# controle_com_2dimmer.net
KiCad netlist of a schematic drawn in EAGLE
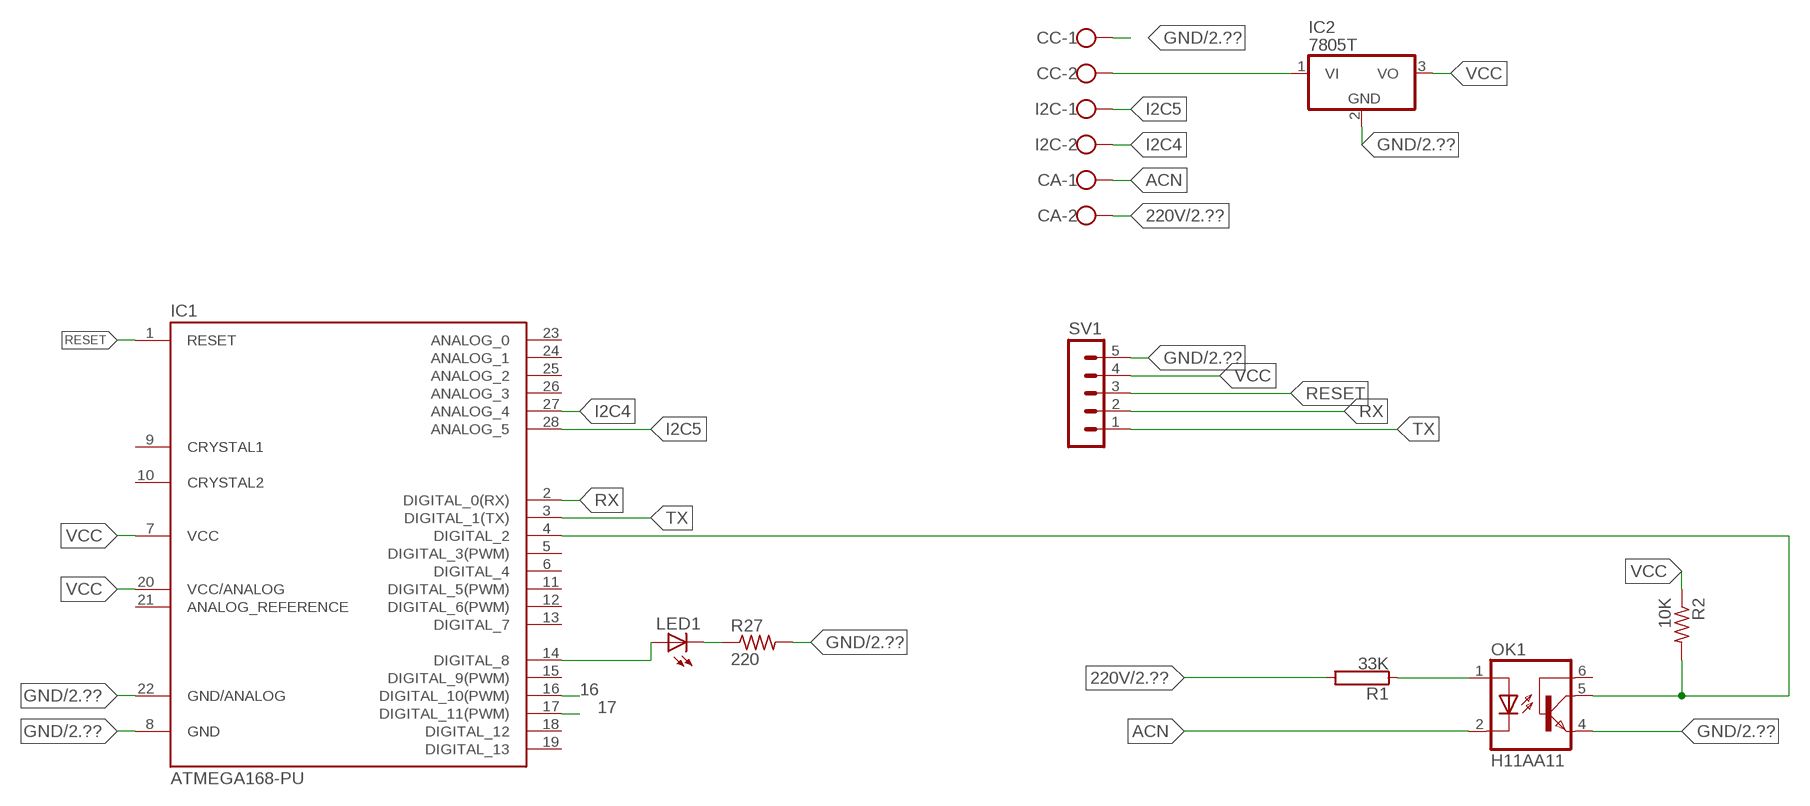
[diagram p0: schematic, sheet 1]
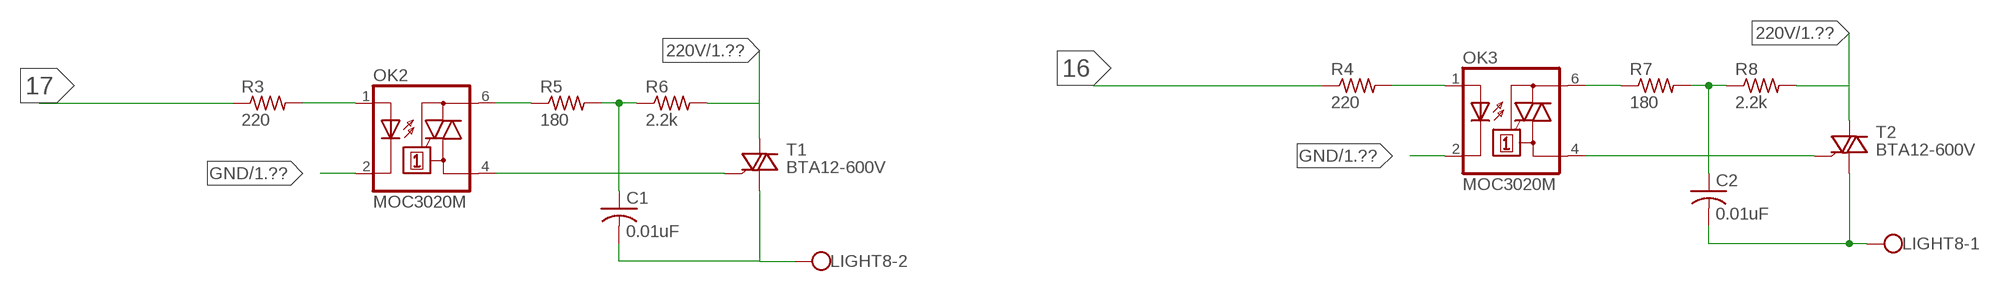
[diagram p1: schematic, sheet 2]

(export (version "E")
  (design (tool "Eeschema 10.0.6"))
  (components
    (comp (ref "CA")
      (value "W237-102")
      (footprint "eagle-import:W237-102")
      (fields (field (name "MPN") "237-102"))
      (libsource (lib "eagle-import") (part "W237-102"))
    )
    (comp (ref "CC")
      (value "W237-102")
      (footprint "eagle-import:W237-102")
      (fields (field (name "MPN") "237-102"))
      (libsource (lib "eagle-import") (part "W237-102"))
    )
    (comp (ref "I2C")
      (value "W237-102")
      (footprint "eagle-import:W237-102")
      (fields (field (name "MPN") "237-102"))
      (libsource (lib "eagle-import") (part "W237-102"))
    )
    (comp (ref "IC1")
      (value "ATMEGA168-PU")
      (footprint "eagle-import:DIL28-3")
      (libsource (lib "eagle-import") (part "ATMEGA168-PU"))
    )
    (comp (ref "IC2")
      (value "7805T")
      (footprint "eagle-import:TO220H")
      (libsource (lib "eagle-import") (part "78T05"))
    )
    (comp (ref "LED1")
      (value "LED3MM")
      (footprint "eagle-import:LED3MM")
      (libsource (lib "eagle-import") (part "LED3MM"))
    )
    (comp (ref "OK1")
      (value "H11AA11")
      (footprint "eagle-import:DIL06")
      (fields (field (name "MPN") "H11A1-M"))
      (libsource (lib "eagle-import") (part "H11AA11"))
    )
    (comp (ref "R1")
      (value "33K")
      (footprint "eagle-import:KH206-8R")
      (libsource (lib "eagle-import") (part "RKH206-8R"))
    )
    (comp (ref "R2")
      (value "10K")
      (footprint "eagle-import:0207_7")
      (libsource (lib "eagle-import") (part "R-US_0207/7"))
    )
    (comp (ref "R27")
      (value "220")
      (footprint "eagle-import:0207_7")
      (libsource (lib "eagle-import") (part "R-US_0207/7"))
    )
    (comp (ref "SV1")
      (value "MA05-1")
      (footprint "eagle-import:MA05-1")
      (libsource (lib "eagle-import") (part "MA05-1"))
    )
    (comp (ref "C1")
      (value "0.01uF")
      (footprint "eagle-import:C075-042X103")
      (libsource (lib "eagle-import") (part "C-US075-042X103"))
    )
    (comp (ref "C2")
      (value "0.01uF")
      (footprint "eagle-import:C075-042X103")
      (libsource (lib "eagle-import") (part "C-US075-042X103"))
    )
    (comp (ref "LIGHT8")
      (value "W237-102")
      (footprint "eagle-import:W237-102")
      (fields (field (name "MPN") "237-102"))
      (libsource (lib "eagle-import") (part "W237-102"))
    )
    (comp (ref "OK2")
      (value "MOC3020M")
      (footprint "eagle-import:DIL06")
      (fields (field (name "MF") "FAIRCHILD SEMICONDUCTOR") (field (name "MPN") "MOC3020-M"))
      (libsource (lib "eagle-import") (part "MOC30M20"))
    )
    (comp (ref "OK3")
      (value "MOC3020M")
      (footprint "eagle-import:DIL06")
      (fields (field (name "MF") "FAIRCHILD SEMICONDUCTOR") (field (name "MPN") "MOC3020-M"))
      (libsource (lib "eagle-import") (part "MOC30M20"))
    )
    (comp (ref "R3")
      (value "220")
      (footprint "eagle-import:0207_7")
      (libsource (lib "eagle-import") (part "R-US_0207/7"))
    )
    (comp (ref "R4")
      (value "220")
      (footprint "eagle-import:0207_7")
      (libsource (lib "eagle-import") (part "R-US_0207/7"))
    )
    (comp (ref "R5")
      (value "180")
      (footprint "eagle-import:0309_10")
      (libsource (lib "eagle-import") (part "R-US_0309/10"))
    )
    (comp (ref "R6")
      (value "2.2k")
      (footprint "eagle-import:0309_10")
      (libsource (lib "eagle-import") (part "R-US_0309/10"))
    )
    (comp (ref "R7")
      (value "180")
      (footprint "eagle-import:0309_10")
      (libsource (lib "eagle-import") (part "R-US_0309/10"))
    )
    (comp (ref "R8")
      (value "2.2k")
      (footprint "eagle-import:0309_10")
      (libsource (lib "eagle-import") (part "R-US_0309/10"))
    )
    (comp (ref "T1")
      (value "BTA12-600V")
      (footprint "eagle-import:TO220V")
      (libsource (lib "eagle-import") (part "BTA12-600V"))
    )
    (comp (ref "T2")
      (value "BTA12-600V")
      (footprint "eagle-import:TO220V")
      (libsource (lib "eagle-import") (part "BTA12-600V"))
    )
  )
  (nets
    (net (code "1") (name "16") (class "Default")
      (node (ref "IC1") (pin "16") (pinfunction "DIGITAL_10(PWM)_16") (pintype "bidirectional"))
      (node (ref "R4") (pin "1") (pinfunction "1_1") (pintype "passive"))
    )
    (net (code "2") (name "17") (class "Default")
      (node (ref "IC1") (pin "17") (pinfunction "DIGITAL_11(PWM)_17") (pintype "bidirectional"))
      (node (ref "R3") (pin "1") (pinfunction "1_1") (pintype "passive"))
    )
    (net (code "3") (name "220V") (class "Default")
      (node (ref "CA") (pin "2") (pinfunction "KL_2") (pintype "passive"))
      (node (ref "R1") (pin "2") (pinfunction "2_2") (pintype "passive"))
      (node (ref "R6") (pin "2") (pinfunction "2_2") (pintype "passive"))
      (node (ref "R8") (pin "2") (pinfunction "2_2") (pintype "passive"))
      (node (ref "T1") (pin "2") (pinfunction "A2_2") (pintype "passive"))
      (node (ref "T2") (pin "2") (pinfunction "A2_2") (pintype "passive"))
    )
    (net (code "4") (name "ACN") (class "Default")
      (node (ref "CA") (pin "1") (pinfunction "KL_1") (pintype "passive"))
      (node (ref "OK1") (pin "2") (pinfunction "C_2") (pintype "passive"))
    )
    (net (code "5") (name "GND") (class "Default")
      (node (ref "CC") (pin "1") (pinfunction "KL_1") (pintype "passive"))
      (node (ref "IC1") (pin "22") (pinfunction "GND/ANALOG_22") (pintype "power_in"))
      (node (ref "IC1") (pin "8") (pinfunction "GND_8") (pintype "power_in"))
      (node (ref "IC2") (pin "2") (pinfunction "GND_2") (pintype "passive"))
      (node (ref "OK1") (pin "4") (pinfunction "EMI_4") (pintype "passive"))
      (node (ref "OK2") (pin "2") (pinfunction "C_2") (pintype "passive"))
      (node (ref "OK3") (pin "2") (pinfunction "C_2") (pintype "passive"))
      (node (ref "R27") (pin "2") (pinfunction "2_2") (pintype "passive"))
      (node (ref "SV1") (pin "5") (pinfunction "5_5") (pintype "passive"))
    )
    (net (code "6") (name "I2C4") (class "Default")
      (node (ref "I2C") (pin "2") (pinfunction "KL_2") (pintype "passive"))
      (node (ref "IC1") (pin "27") (pinfunction "ANALOG_4_27") (pintype "bidirectional"))
    )
    (net (code "7") (name "I2C5") (class "Default")
      (node (ref "I2C") (pin "1") (pinfunction "KL_1") (pintype "passive"))
      (node (ref "IC1") (pin "28") (pinfunction "ANALOG_5_28") (pintype "bidirectional"))
    )
    (net (code "8") (name "Net-(C1-Pad1)") (class "Default")
      (node (ref "C1") (pin "1") (pinfunction "1_1") (pintype "passive"))
      (node (ref "R5") (pin "2") (pinfunction "2_2") (pintype "passive"))
      (node (ref "R6") (pin "1") (pinfunction "1_1") (pintype "passive"))
    )
    (net (code "9") (name "Net-(C2-Pad1)") (class "Default")
      (node (ref "C2") (pin "1") (pinfunction "1_1") (pintype "passive"))
      (node (ref "R7") (pin "2") (pinfunction "2_2") (pintype "passive"))
      (node (ref "R8") (pin "1") (pinfunction "1_1") (pintype "passive"))
    )
    (net (code "10") (name "Net-(CCB-KL)") (class "Default")
      (node (ref "CC") (pin "2") (pinfunction "KL_2") (pintype "passive"))
      (node (ref "IC2") (pin "1") (pinfunction "VI_1") (pintype "input"))
    )
    (net (code "11") (name "Net-(IC1-DIGITAL_2)") (class "Default")
      (node (ref "IC1") (pin "4") (pinfunction "DIGITAL_2_4") (pintype "bidirectional"))
      (node (ref "OK1") (pin "5") (pinfunction "COL_5") (pintype "passive"))
      (node (ref "R2") (pin "2") (pinfunction "2_2") (pintype "passive"))
    )
    (net (code "12") (name "Net-(IC1-DIGITAL_8)") (class "Default")
      (node (ref "IC1") (pin "14") (pinfunction "DIGITAL_8_14") (pintype "bidirectional"))
      (node (ref "LED1") (pin "A") (pinfunction "A_A") (pintype "passive"))
    )
    (net (code "13") (name "Net-(LED1-C)") (class "Default")
      (node (ref "LED1") (pin "K") (pinfunction "C_K") (pintype "passive"))
      (node (ref "R27") (pin "1") (pinfunction "1_1") (pintype "passive"))
    )
    (net (code "14") (name "Net-(LIGHT8A-KL)") (class "Default")
      (node (ref "C2") (pin "2") (pinfunction "2_2") (pintype "passive"))
      (node (ref "LIGHT8") (pin "1") (pinfunction "KL_1") (pintype "passive"))
      (node (ref "T2") (pin "1") (pinfunction "A1_1") (pintype "passive"))
    )
    (net (code "15") (name "Net-(LIGHT8B-KL)") (class "Default")
      (node (ref "C1") (pin "2") (pinfunction "2_2") (pintype "passive"))
      (node (ref "LIGHT8") (pin "2") (pinfunction "KL_2") (pintype "passive"))
      (node (ref "T1") (pin "1") (pinfunction "A1_1") (pintype "passive"))
    )
    (net (code "16") (name "Net-(OK1-A)") (class "Default")
      (node (ref "OK1") (pin "1") (pinfunction "A_1") (pintype "passive"))
      (node (ref "R1") (pin "1") (pinfunction "1_1") (pintype "passive"))
    )
    (net (code "17") (name "Net-(OK2-A)") (class "Default")
      (node (ref "OK2") (pin "1") (pinfunction "A_1") (pintype "passive"))
      (node (ref "R3") (pin "2") (pinfunction "2_2") (pintype "passive"))
    )
    (net (code "18") (name "Net-(OK2-A1)") (class "Default")
      (node (ref "OK2") (pin "4") (pinfunction "A1_4") (pintype "passive"))
      (node (ref "T1") (pin "3") (pinfunction "G_3") (pintype "passive"))
    )
    (net (code "19") (name "Net-(OK2-A2)") (class "Default")
      (node (ref "OK2") (pin "6") (pinfunction "A2_6") (pintype "passive"))
      (node (ref "R5") (pin "1") (pinfunction "1_1") (pintype "passive"))
    )
    (net (code "20") (name "Net-(OK3-A)") (class "Default")
      (node (ref "OK3") (pin "1") (pinfunction "A_1") (pintype "passive"))
      (node (ref "R4") (pin "2") (pinfunction "2_2") (pintype "passive"))
    )
    (net (code "21") (name "Net-(OK3-A1)") (class "Default")
      (node (ref "OK3") (pin "4") (pinfunction "A1_4") (pintype "passive"))
      (node (ref "T2") (pin "3") (pinfunction "G_3") (pintype "passive"))
    )
    (net (code "22") (name "Net-(OK3-A2)") (class "Default")
      (node (ref "OK3") (pin "6") (pinfunction "A2_6") (pintype "passive"))
      (node (ref "R7") (pin "1") (pinfunction "1_1") (pintype "passive"))
    )
    (net (code "23") (name "RESET") (class "Default")
      (node (ref "IC1") (pin "1") (pinfunction "RESET_1") (pintype "bidirectional"))
      (node (ref "SV1") (pin "3") (pinfunction "3_3") (pintype "passive"))
    )
    (net (code "24") (name "RX") (class "Default")
      (node (ref "IC1") (pin "2") (pinfunction "DIGITAL_0(RX)_2") (pintype "bidirectional"))
      (node (ref "SV1") (pin "2") (pinfunction "2_2") (pintype "passive"))
    )
    (net (code "25") (name "TX") (class "Default")
      (node (ref "IC1") (pin "3") (pinfunction "DIGITAL_1(TX)_3") (pintype "bidirectional"))
      (node (ref "SV1") (pin "1") (pinfunction "1_1") (pintype "passive"))
    )
    (net (code "26") (name "VCC") (class "Default")
      (node (ref "IC1") (pin "20") (pinfunction "VCC/ANALOG_20") (pintype "passive"))
      (node (ref "IC1") (pin "7") (pinfunction "VCC_7") (pintype "power_in"))
      (node (ref "IC2") (pin "3") (pinfunction "VO_3") (pintype "passive"))
      (node (ref "R2") (pin "1") (pinfunction "1_1") (pintype "passive"))
      (node (ref "SV1") (pin "4") (pinfunction "4_4") (pintype "passive"))
    )
    (net (code "27") (name "unconnected-(IC1-ANALOG_0-Pad23)") (class "Default")
      (node (ref "IC1") (pin "23") (pinfunction "ANALOG_0_23") (pintype "bidirectional"))
    )
    (net (code "28") (name "unconnected-(IC1-ANALOG_1-Pad24)") (class "Default")
      (node (ref "IC1") (pin "24") (pinfunction "ANALOG_1_24") (pintype "bidirectional"))
    )
    (net (code "29") (name "unconnected-(IC1-ANALOG_2-Pad25)") (class "Default")
      (node (ref "IC1") (pin "25") (pinfunction "ANALOG_2_25") (pintype "bidirectional"))
    )
    (net (code "30") (name "unconnected-(IC1-ANALOG_3-Pad26)") (class "Default")
      (node (ref "IC1") (pin "26") (pinfunction "ANALOG_3_26") (pintype "bidirectional"))
    )
    (net (code "31") (name "unconnected-(IC1-ANALOG_REFERENCE-Pad21)") (class "Default")
      (node (ref "IC1") (pin "21") (pinfunction "ANALOG_REFERENCE_21") (pintype "passive"))
    )
    (net (code "32") (name "unconnected-(IC1-CRYSTAL1-Pad9)") (class "Default")
      (node (ref "IC1") (pin "9") (pinfunction "CRYSTAL1_9") (pintype "bidirectional"))
    )
    (net (code "33") (name "unconnected-(IC1-CRYSTAL2-Pad10)") (class "Default")
      (node (ref "IC1") (pin "10") (pinfunction "CRYSTAL2_10") (pintype "bidirectional"))
    )
    (net (code "34") (name "unconnected-(IC1-DIGITAL_3(PWM)-Pad5)") (class "Default")
      (node (ref "IC1") (pin "5") (pinfunction "DIGITAL_3(PWM)_5") (pintype "bidirectional"))
    )
    (net (code "35") (name "unconnected-(IC1-DIGITAL_4-Pad6)") (class "Default")
      (node (ref "IC1") (pin "6") (pinfunction "DIGITAL_4_6") (pintype "bidirectional"))
    )
    (net (code "36") (name "unconnected-(IC1-DIGITAL_5(PWM)-Pad11)") (class "Default")
      (node (ref "IC1") (pin "11") (pinfunction "DIGITAL_5(PWM)_11") (pintype "bidirectional"))
    )
    (net (code "37") (name "unconnected-(IC1-DIGITAL_6(PWM)-Pad12)") (class "Default")
      (node (ref "IC1") (pin "12") (pinfunction "DIGITAL_6(PWM)_12") (pintype "bidirectional"))
    )
    (net (code "38") (name "unconnected-(IC1-DIGITAL_7-Pad13)") (class "Default")
      (node (ref "IC1") (pin "13") (pinfunction "DIGITAL_7_13") (pintype "bidirectional"))
    )
    (net (code "39") (name "unconnected-(IC1-DIGITAL_9(PWM)-Pad15)") (class "Default")
      (node (ref "IC1") (pin "15") (pinfunction "DIGITAL_9(PWM)_15") (pintype "bidirectional"))
    )
    (net (code "40") (name "unconnected-(IC1-DIGITAL_12-Pad18)") (class "Default")
      (node (ref "IC1") (pin "18") (pinfunction "DIGITAL_12_18") (pintype "bidirectional"))
    )
    (net (code "41") (name "unconnected-(IC1-DIGITAL_13-Pad19)") (class "Default")
      (node (ref "IC1") (pin "19") (pinfunction "DIGITAL_13_19") (pintype "bidirectional"))
    )
    (net (code "42") (name "unconnected-(OK1-BAS-Pad6)") (class "Default")
      (node (ref "OK1") (pin "6") (pinfunction "BAS_6") (pintype "passive"))
    )
  )
)
